# schematic.net
KiCad netlist of a schematic drawn in Altium Designer
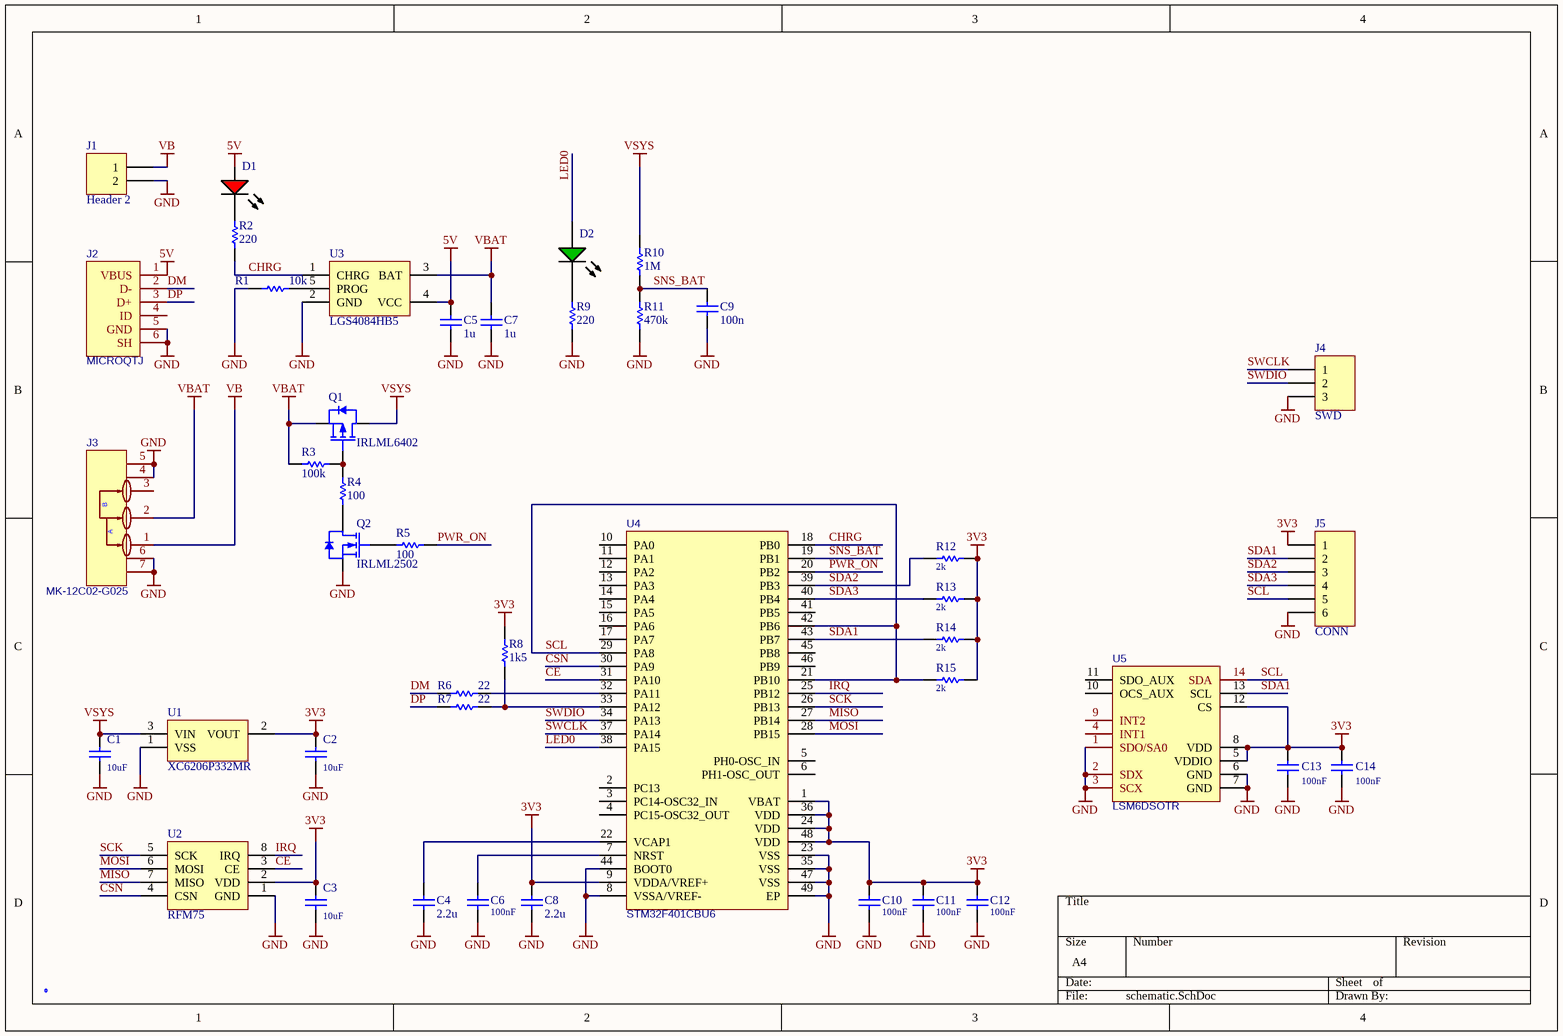
[diagram p0: schematic.SchDoc]

(export (version "E")
  (design (tool "Eeschema 10.0.6"))
  (components
    (comp (ref "C1")
      (value "10uF")
      (footprint "C0603")
      (libsource (lib "Miscellaneous Devices") (part "CAP"))
    )
    (comp (ref "C2")
      (value "10uF")
      (footprint "C0603")
      (libsource (lib "Miscellaneous Devices") (part "CAP"))
    )
    (comp (ref "C3")
      (value "10uF")
      (footprint "C0805")
      (libsource (lib "Miscellaneous Devices") (part "CAP"))
    )
    (comp (ref "C4")
      (value "2.2u")
      (footprint "C0603")
      (libsource (lib "Miscellaneous Devices") (part "Cap"))
    )
    (comp (ref "C5") (value "1u") (footprint "C0805") (libsource (lib "Miscellaneous Devices") (part "Cap")))
    (comp (ref "C6")
      (value "100nF")
      (footprint "C0402")
      (libsource (lib "Miscellaneous Devices") (part "CAP"))
    )
    (comp (ref "C7") (value "1u") (footprint "C0805") (libsource (lib "Miscellaneous Devices") (part "Cap")))
    (comp (ref "C8")
      (value "2.2u")
      (footprint "C0603")
      (libsource (lib "Miscellaneous Devices") (part "Cap"))
    )
    (comp (ref "C9")
      (value "100n")
      (footprint "C0402")
      (libsource (lib "Miscellaneous Devices") (part "Cap"))
    )
    (comp (ref "C10")
      (value "100nF")
      (footprint "C0402")
      (libsource (lib "Miscellaneous Devices") (part "CAP"))
    )
    (comp (ref "C11")
      (value "100nF")
      (footprint "C0402")
      (libsource (lib "Miscellaneous Devices") (part "CAP"))
    )
    (comp (ref "C12")
      (value "100nF")
      (footprint "C0402")
      (libsource (lib "Miscellaneous Devices") (part "CAP"))
    )
    (comp (ref "C13")
      (value "100nF")
      (footprint "C0402")
      (fields (field (name "LCSC PART NUMBER") "C131394"))
      (libsource (lib "Miscellaneous Devices") (part "CAP"))
    )
    (comp (ref "C14")
      (value "100nF")
      (footprint "C0402")
      (fields (field (name "LCSC PART NUMBER") "C131394"))
      (libsource (lib "Miscellaneous Devices") (part "CAP"))
    )
    (comp (ref "D1")
      (value "RED")
      (footprint "LED-0603-RED")
      (description "LED 0603 RED")
      (libsource (lib "Miscellaneous Devices") (part "LED-0603-RED"))
    )
    (comp (ref "D2")
      (value "GRN")
      (footprint "LED-0603-GRN")
      (description "LED 0603 GRN")
      (libsource (lib "Miscellaneous Devices") (part "LED-0603-GREEN"))
    )
    (comp (ref "J1")
      (value "Header 2")
      (footprint "HDR-1X2_2.54")
      (libsource (lib "Schlib1") (part "Header 2"))
    )
    (comp (ref "J2")
      (value "MICROQTJ")
      (footprint "CONN-USB-MICRO_#1")
      (libsource (lib "Schlib2") (part "MICROQTJ"))
    )
    (comp (ref "J3")
      (value "MK-12C02-G025")
      (footprint "SW-SMD_MK-12C02-G025")
      (fields (field (name "LCSC PART NUMBER") "C778186"))
      (libsource (lib "Schlib1") (part "MK-12C02-G025"))
    )
    (comp (ref "J4")
      (value "SWD")
      (footprint "HDR-1x3-P1.25")
      (libsource (lib "Miscellaneous Devices") (part "Header 3"))
    )
    (comp (ref "J5") (value "CONN") (footprint "HDR-1x6-P1.25") (libsource (lib "Schlib1") (part "Header 3")))
    (comp (ref "LOGO1") (value "LOGO") (footprint "LOGO") (libsource (lib "Schlib1") (part "LOGO")))
    (comp (ref "Q1") (value "IRLML6402") (footprint "SOT-23") (libsource (lib "") (part "2N7002_1")))
    (comp (ref "Q2")
      (value "IRLML2502")
      (footprint "SOT-23")
      (libsource (lib "Miscellaneous Devices") (part "2N7002"))
    )
    (comp (ref "R1")
      (value "10k")
      (footprint "R0402")
      (libsource (lib "Miscellaneous Devices") (part "Res1"))
    )
    (comp (ref "R2")
      (value "220")
      (footprint "R0402")
      (libsource (lib "Miscellaneous Devices") (part "Res1"))
    )
    (comp (ref "R3")
      (value "100k")
      (footprint "R0402")
      (libsource (lib "Miscellaneous Devices") (part "Res1"))
    )
    (comp (ref "R4")
      (value "100")
      (footprint "R0402")
      (libsource (lib "Miscellaneous Devices") (part "Res1"))
    )
    (comp (ref "R5")
      (value "100")
      (footprint "R0402")
      (libsource (lib "Miscellaneous Devices") (part "Res1"))
    )
    (comp (ref "R6") (value "22") (footprint "R0402") (libsource (lib "Miscellaneous Devices") (part "Res1")))
    (comp (ref "R7") (value "22") (footprint "R0402") (libsource (lib "Miscellaneous Devices") (part "Res1")))
    (comp (ref "R8")
      (value "1k5")
      (footprint "R0402")
      (libsource (lib "Miscellaneous Devices") (part "Res1"))
    )
    (comp (ref "R9")
      (value "220")
      (footprint "R0402")
      (libsource (lib "Miscellaneous Devices") (part "Res1"))
    )
    (comp (ref "R10")
      (value "1M")
      (footprint "R0402")
      (libsource (lib "Miscellaneous Devices") (part "Res1"))
    )
    (comp (ref "R11")
      (value "470k")
      (footprint "R0402")
      (libsource (lib "Miscellaneous Devices") (part "Res1"))
    )
    (comp (ref "R12") (value "2k") (footprint "R0402") (libsource (lib "Miscellaneous Devices") (part "RES")))
    (comp (ref "R13") (value "2k") (footprint "R0402") (libsource (lib "Miscellaneous Devices") (part "RES")))
    (comp (ref "R14") (value "2k") (footprint "R0402") (libsource (lib "Miscellaneous Devices") (part "RES")))
    (comp (ref "R15") (value "2k") (footprint "R0402") (libsource (lib "Miscellaneous Devices") (part "RES")))
    (comp (ref "U1")
      (value "XC6206P332MR")
      (footprint "SOT-23")
      (libsource (lib "Schlib1") (part "Component_4_1"))
    )
    (comp (ref "U2") (value "RFM75") (footprint "RFM75") (libsource (lib "Schlib1") (part "RFM75")))
    (comp (ref "U3")
      (value "LGS4084HB5")
      (footprint "SOT-23-5")
      (libsource (lib "Schlib1") (part "LGS4084HB5"))
    )
    (comp (ref "U4")
      (value "STM32F401CBU6")
      (footprint "UFQFPN-48_L7.0-W7.0")
      (fields (field (name "LCSC PART NUMBER") "C118825"))
      (libsource (lib "Schlib1") (part "STM32F401CBU6"))
    )
    (comp (ref "U5")
      (value "LSM6DSOTR")
      (footprint "LGA-14_L3.0-W2.5-P0.50-TL")
      (fields (field (name "LCSC PART NUMBER") "C2655100"))
      (libsource (lib "Schlib1") (part "LSM6DSOTR"))
    )
  )
  (nets
    (net (code "1") (name "/CE") (class "Default")
      (node (ref "U2") (pin "3") (pinfunction "CE_3") (pintype "passive"))
      (node (ref "U4") (pin "31") (pinfunction "PA10_31") (pintype "passive"))
    )
    (net (code "2") (name "/CHRG") (class "Default")
      (node (ref "R2") (pin "1") (pinfunction "1_1") (pintype "passive"))
      (node (ref "U3") (pin "1") (pinfunction "CHRG_1") (pintype "passive"))
      (node (ref "U4") (pin "18") (pinfunction "PB0_18") (pintype "passive"))
    )
    (net (code "3") (name "/CSN") (class "Default")
      (node (ref "U2") (pin "4") (pinfunction "CSN_4") (pintype "passive"))
      (node (ref "U4") (pin "30") (pinfunction "PA9_30") (pintype "passive"))
    )
    (net (code "4") (name "/DM") (class "Default")
      (node (ref "J2") (pin "2") (pinfunction "D-_2") (pintype "passive"))
      (node (ref "R6") (pin "2") (pinfunction "2_2") (pintype "passive"))
    )
    (net (code "5") (name "/DP") (class "Default")
      (node (ref "J2") (pin "3") (pinfunction "D+_3") (pintype "passive"))
      (node (ref "R7") (pin "2") (pinfunction "2_2") (pintype "passive"))
    )
    (net (code "6") (name "/IRQ") (class "Default")
      (node (ref "U2") (pin "8") (pinfunction "IRQ_8") (pintype "passive"))
      (node (ref "U4") (pin "25") (pinfunction "PB12_25") (pintype "passive"))
    )
    (net (code "7") (name "/LED0") (class "Default")
      (node (ref "D2") (pin "1") (pinfunction "A_1") (pintype "passive"))
      (node (ref "U4") (pin "38") (pinfunction "PA15_38") (pintype "passive"))
    )
    (net (code "8") (name "/MISO") (class "Default")
      (node (ref "U2") (pin "7") (pinfunction "MISO_7") (pintype "passive"))
      (node (ref "U4") (pin "27") (pinfunction "PB14_27") (pintype "passive"))
    )
    (net (code "9") (name "/MOSI") (class "Default")
      (node (ref "U2") (pin "6") (pinfunction "MOSI_6") (pintype "passive"))
      (node (ref "U4") (pin "28") (pinfunction "PB15_28") (pintype "passive"))
    )
    (net (code "10") (name "/PWR_ON") (class "Default")
      (node (ref "R5") (pin "1") (pinfunction "1_1") (pintype "passive"))
      (node (ref "U4") (pin "20") (pinfunction "PB2_20") (pintype "passive"))
    )
    (net (code "11") (name "/SCK") (class "Default")
      (node (ref "U2") (pin "5") (pinfunction "SCK_5") (pintype "passive"))
      (node (ref "U4") (pin "26") (pinfunction "PB13_26") (pintype "passive"))
    )
    (net (code "12") (name "/SCL") (class "Default")
      (node (ref "J5") (pin "5") (pinfunction "5_5") (pintype "passive"))
      (node (ref "R15") (pin "2") (pinfunction "2_2") (pintype "passive"))
      (node (ref "U4") (pin "21") (pinfunction "PB10_21") (pintype "passive"))
      (node (ref "U4") (pin "29") (pinfunction "PA8_29") (pintype "passive"))
      (node (ref "U4") (pin "42") (pinfunction "PB6_42") (pintype "passive"))
      (node (ref "U5") (pin "14") (pinfunction "SDA_14") (pintype "passive"))
    )
    (net (code "13") (name "/SDA1") (class "Default")
      (node (ref "J5") (pin "2") (pinfunction "2_2") (pintype "passive"))
      (node (ref "R14") (pin "2") (pinfunction "2_2") (pintype "passive"))
      (node (ref "U4") (pin "43") (pinfunction "PB7_43") (pintype "passive"))
      (node (ref "U5") (pin "13") (pinfunction "SCL_13") (pintype "passive"))
    )
    (net (code "14") (name "/SDA2") (class "Default")
      (node (ref "J5") (pin "3") (pinfunction "3_3") (pintype "passive"))
      (node (ref "R12") (pin "2") (pinfunction "2_2") (pintype "passive"))
      (node (ref "U4") (pin "39") (pinfunction "PB3_39") (pintype "passive"))
    )
    (net (code "15") (name "/SDA3") (class "Default")
      (node (ref "J5") (pin "4") (pinfunction "4_4") (pintype "passive"))
      (node (ref "R13") (pin "2") (pinfunction "2_2") (pintype "passive"))
      (node (ref "U4") (pin "40") (pinfunction "PB4_40") (pintype "passive"))
    )
    (net (code "16") (name "/SNS_BAT") (class "Default")
      (node (ref "C9") (pin "2") (pinfunction "2_2") (pintype "passive"))
      (node (ref "R10") (pin "1") (pinfunction "1_1") (pintype "passive"))
      (node (ref "R11") (pin "2") (pinfunction "2_2") (pintype "passive"))
      (node (ref "U4") (pin "19") (pinfunction "PB1_19") (pintype "passive"))
    )
    (net (code "17") (name "/SWCLK") (class "Default")
      (node (ref "J4") (pin "1") (pinfunction "1_1") (pintype "passive"))
      (node (ref "U4") (pin "37") (pinfunction "PA14_37") (pintype "passive"))
    )
    (net (code "18") (name "/SWDIO") (class "Default")
      (node (ref "J4") (pin "2") (pinfunction "2_2") (pintype "passive"))
      (node (ref "U4") (pin "34") (pinfunction "PA13_34") (pintype "passive"))
    )
    (net (code "19") (name "3V3") (class "Default")
      (node (ref "C10") (pin "2") (pinfunction "2_2") (pintype "passive"))
      (node (ref "C11") (pin "2") (pinfunction "2_2") (pintype "passive"))
      (node (ref "C12") (pin "2") (pinfunction "2_2") (pintype "passive"))
      (node (ref "C13") (pin "2") (pinfunction "2_2") (pintype "passive"))
      (node (ref "C14") (pin "2") (pinfunction "2_2") (pintype "passive"))
      (node (ref "C2") (pin "2") (pinfunction "2_2") (pintype "passive"))
      (node (ref "C3") (pin "2") (pinfunction "2_2") (pintype "passive"))
      (node (ref "C8") (pin "2") (pinfunction "2_2") (pintype "passive"))
      (node (ref "J5") (pin "1") (pinfunction "1_1") (pintype "passive"))
      (node (ref "R12") (pin "1") (pinfunction "1_1") (pintype "passive"))
      (node (ref "R13") (pin "1") (pinfunction "1_1") (pintype "passive"))
      (node (ref "R14") (pin "1") (pinfunction "1_1") (pintype "passive"))
      (node (ref "R15") (pin "1") (pinfunction "1_1") (pintype "passive"))
      (node (ref "R8") (pin "1") (pinfunction "1_1") (pintype "passive"))
      (node (ref "U1") (pin "2") (pinfunction "VOUT_2") (pintype "passive"))
      (node (ref "U2") (pin "2") (pinfunction "VDD_2") (pintype "passive"))
      (node (ref "U4") (pin "1") (pinfunction "VBAT_1") (pintype "passive"))
      (node (ref "U4") (pin "24") (pinfunction "VDD_24") (pintype "passive"))
      (node (ref "U4") (pin "36") (pinfunction "VDD_36") (pintype "passive"))
      (node (ref "U4") (pin "48") (pinfunction "VDD_48") (pintype "passive"))
      (node (ref "U4") (pin "9") (pinfunction "VDDA/VREF+_9") (pintype "passive"))
      (node (ref "U5") (pin "12") (pinfunction "CS_12") (pintype "passive"))
      (node (ref "U5") (pin "5") (pinfunction "VDDIO_5") (pintype "passive"))
      (node (ref "U5") (pin "8") (pinfunction "VDD_8") (pintype "passive"))
    )
    (net (code "20") (name "5V") (class "Default")
      (node (ref "C5") (pin "2") (pinfunction "2_2") (pintype "passive"))
      (node (ref "D1") (pin "1") (pinfunction "A_1") (pintype "passive"))
      (node (ref "J2") (pin "1") (pinfunction "VBUS_1") (pintype "passive"))
      (node (ref "U3") (pin "4") (pinfunction "VCC_4") (pintype "passive"))
    )
    (net (code "21") (name "GND") (class "Default")
      (node (ref "C1") (pin "1") (pinfunction "1_1") (pintype "passive"))
      (node (ref "C10") (pin "1") (pinfunction "1_1") (pintype "passive"))
      (node (ref "C11") (pin "1") (pinfunction "1_1") (pintype "passive"))
      (node (ref "C12") (pin "1") (pinfunction "1_1") (pintype "passive"))
      (node (ref "C13") (pin "1") (pinfunction "1_1") (pintype "passive"))
      (node (ref "C14") (pin "1") (pinfunction "1_1") (pintype "passive"))
      (node (ref "C2") (pin "1") (pinfunction "1_1") (pintype "passive"))
      (node (ref "C3") (pin "1") (pinfunction "1_1") (pintype "passive"))
      (node (ref "C4") (pin "1") (pinfunction "1_1") (pintype "passive"))
      (node (ref "C5") (pin "1") (pinfunction "1_1") (pintype "passive"))
      (node (ref "C6") (pin "1") (pinfunction "1_1") (pintype "passive"))
      (node (ref "C7") (pin "1") (pinfunction "1_1") (pintype "passive"))
      (node (ref "C8") (pin "1") (pinfunction "1_1") (pintype "passive"))
      (node (ref "C9") (pin "1") (pinfunction "1_1") (pintype "passive"))
      (node (ref "J1") (pin "2") (pinfunction "2_2") (pintype "passive"))
      (node (ref "J2") (pin "5") (pinfunction "GND_5") (pintype "passive"))
      (node (ref "J2") (pin "6") (pinfunction "SH_6") (pintype "passive"))
      (node (ref "J3") (pin "4") (pinfunction "4_4") (pintype "passive"))
      (node (ref "J3") (pin "5") (pinfunction "5_5") (pintype "passive"))
      (node (ref "J3") (pin "6") (pinfunction "6_6") (pintype "passive"))
      (node (ref "J3") (pin "7") (pinfunction "7_7") (pintype "passive"))
      (node (ref "J4") (pin "3") (pinfunction "3_3") (pintype "passive"))
      (node (ref "J5") (pin "6") (pinfunction "6_6") (pintype "passive"))
      (node (ref "Q2") (pin "2") (pinfunction "SOURCE_2") (pintype "passive"))
      (node (ref "R1") (pin "2") (pinfunction "2_2") (pintype "passive"))
      (node (ref "R11") (pin "1") (pinfunction "1_1") (pintype "passive"))
      (node (ref "R9") (pin "1") (pinfunction "1_1") (pintype "passive"))
      (node (ref "U1") (pin "1") (pinfunction "VSS_1") (pintype "passive"))
      (node (ref "U2") (pin "1") (pinfunction "GND_1") (pintype "passive"))
      (node (ref "U3") (pin "2") (pinfunction "GND_2") (pintype "passive"))
      (node (ref "U4") (pin "23") (pinfunction "VSS_23") (pintype "passive"))
      (node (ref "U4") (pin "35") (pinfunction "VSS_35") (pintype "passive"))
      (node (ref "U4") (pin "44") (pinfunction "BOOT0_44") (pintype "passive"))
      (node (ref "U4") (pin "47") (pinfunction "VSS_47") (pintype "passive"))
      (node (ref "U4") (pin "49") (pinfunction "EP_49") (pintype "passive"))
      (node (ref "U4") (pin "8") (pinfunction "VSSA/VREF-_8") (pintype "passive"))
      (node (ref "U5") (pin "1") (pinfunction "SDO/SA0_1") (pintype "passive"))
      (node (ref "U5") (pin "2") (pinfunction "SDX_2") (pintype "passive"))
      (node (ref "U5") (pin "3") (pinfunction "SCX_3") (pintype "passive"))
      (node (ref "U5") (pin "6") (pinfunction "GND_6") (pintype "passive"))
      (node (ref "U5") (pin "7") (pinfunction "GND_7") (pintype "passive"))
    )
    (net (code "22") (name "Net-(D1-K)") (class "Default")
      (node (ref "D1") (pin "2") (pinfunction "K_2") (pintype "passive"))
      (node (ref "R2") (pin "2") (pinfunction "2_2") (pintype "passive"))
    )
    (net (code "23") (name "Net-(D2-K)") (class "Default")
      (node (ref "D2") (pin "2") (pinfunction "K_2") (pintype "passive"))
      (node (ref "R9") (pin "2") (pinfunction "2_2") (pintype "passive"))
    )
    (net (code "24") (name "Net-(Q1-GATE)") (class "Default")
      (node (ref "Q1") (pin "1") (pinfunction "GATE_1") (pintype "passive"))
      (node (ref "R3") (pin "1") (pinfunction "1_1") (pintype "passive"))
      (node (ref "R4") (pin "2") (pinfunction "2_2") (pintype "passive"))
    )
    (net (code "25") (name "Net-(Q2-DRAIN)") (class "Default")
      (node (ref "Q2") (pin "3") (pinfunction "DRAIN_3") (pintype "passive"))
      (node (ref "R4") (pin "1") (pinfunction "1_1") (pintype "passive"))
    )
    (net (code "26") (name "Net-(Q2-GATE)") (class "Default")
      (node (ref "Q2") (pin "1") (pinfunction "GATE_1") (pintype "passive"))
      (node (ref "R5") (pin "2") (pinfunction "2_2") (pintype "passive"))
    )
    (net (code "27") (name "Net-(U3-PROG)") (class "Default")
      (node (ref "R1") (pin "1") (pinfunction "1_1") (pintype "passive"))
      (node (ref "U3") (pin "5") (pinfunction "PROG_5") (pintype "passive"))
    )
    (net (code "28") (name "Net-(U4-NRST)") (class "Default")
      (node (ref "C6") (pin "2") (pinfunction "2_2") (pintype "passive"))
      (node (ref "U4") (pin "7") (pinfunction "NRST_7") (pintype "passive"))
    )
    (net (code "29") (name "Net-(U4-PA11)") (class "Default")
      (node (ref "R6") (pin "1") (pinfunction "1_1") (pintype "passive"))
      (node (ref "U4") (pin "32") (pinfunction "PA11_32") (pintype "passive"))
    )
    (net (code "30") (name "Net-(U4-PA12)") (class "Default")
      (node (ref "R7") (pin "1") (pinfunction "1_1") (pintype "passive"))
      (node (ref "R8") (pin "2") (pinfunction "2_2") (pintype "passive"))
      (node (ref "U4") (pin "33") (pinfunction "PA12_33") (pintype "passive"))
    )
    (net (code "31") (name "Net-(U4-VCAP1)") (class "Default")
      (node (ref "C4") (pin "2") (pinfunction "2_2") (pintype "passive"))
      (node (ref "U4") (pin "22") (pinfunction "VCAP1_22") (pintype "passive"))
    )
    (net (code "32") (name "VB") (class "Default")
      (node (ref "J1") (pin "1") (pinfunction "1_1") (pintype "passive"))
      (node (ref "J3") (pin "1") (pinfunction "1_1") (pintype "passive"))
    )
    (net (code "33") (name "VBAT") (class "Default")
      (node (ref "C7") (pin "2") (pinfunction "2_2") (pintype "passive"))
      (node (ref "J3") (pin "2") (pinfunction "2_2") (pintype "passive"))
      (node (ref "Q1") (pin "2") (pinfunction "SOURCE_2") (pintype "passive"))
      (node (ref "R3") (pin "2") (pinfunction "2_2") (pintype "passive"))
      (node (ref "U3") (pin "3") (pinfunction "BAT_3") (pintype "passive"))
    )
    (net (code "34") (name "VSYS") (class "Default")
      (node (ref "C1") (pin "2") (pinfunction "2_2") (pintype "passive"))
      (node (ref "Q1") (pin "3") (pinfunction "DRAIN_3") (pintype "passive"))
      (node (ref "R10") (pin "2") (pinfunction "2_2") (pintype "passive"))
      (node (ref "U1") (pin "3") (pinfunction "VIN_3") (pintype "passive"))
    )
    (net (code "35") (name "unconnected-(J2-ID-Pad4)") (class "Default")
      (node (ref "J2") (pin "4") (pinfunction "ID_4") (pintype "passive"))
    )
    (net (code "36") (name "unconnected-(J3-Pad3)") (class "Default")
      (node (ref "J3") (pin "3") (pinfunction "3_3") (pintype "passive"))
    )
    (net (code "37") (name "unconnected-(U4-PA0-Pad10)") (class "Default")
      (node (ref "U4") (pin "10") (pinfunction "PA0_10") (pintype "passive"))
    )
    (net (code "38") (name "unconnected-(U4-PA1-Pad11)") (class "Default")
      (node (ref "U4") (pin "11") (pinfunction "PA1_11") (pintype "passive"))
    )
    (net (code "39") (name "unconnected-(U4-PA2-Pad12)") (class "Default")
      (node (ref "U4") (pin "12") (pinfunction "PA2_12") (pintype "passive"))
    )
    (net (code "40") (name "unconnected-(U4-PA3-Pad13)") (class "Default")
      (node (ref "U4") (pin "13") (pinfunction "PA3_13") (pintype "passive"))
    )
    (net (code "41") (name "unconnected-(U4-PA4-Pad14)") (class "Default")
      (node (ref "U4") (pin "14") (pinfunction "PA4_14") (pintype "passive"))
    )
    (net (code "42") (name "unconnected-(U4-PA5-Pad15)") (class "Default")
      (node (ref "U4") (pin "15") (pinfunction "PA5_15") (pintype "passive"))
    )
    (net (code "43") (name "unconnected-(U4-PA6-Pad16)") (class "Default")
      (node (ref "U4") (pin "16") (pinfunction "PA6_16") (pintype "passive"))
    )
    (net (code "44") (name "unconnected-(U4-PA7-Pad17)") (class "Default")
      (node (ref "U4") (pin "17") (pinfunction "PA7_17") (pintype "passive"))
    )
    (net (code "45") (name "unconnected-(U4-PB5-Pad41)") (class "Default")
      (node (ref "U4") (pin "41") (pinfunction "PB5_41") (pintype "passive"))
    )
    (net (code "46") (name "unconnected-(U4-PB8-Pad45)") (class "Default")
      (node (ref "U4") (pin "45") (pinfunction "PB8_45") (pintype "passive"))
    )
    (net (code "47") (name "unconnected-(U4-PB9-Pad46)") (class "Default")
      (node (ref "U4") (pin "46") (pinfunction "PB9_46") (pintype "passive"))
    )
    (net (code "48") (name "unconnected-(U4-PC13-Pad2)") (class "Default")
      (node (ref "U4") (pin "2") (pinfunction "PC13_2") (pintype "passive"))
    )
    (net (code "49") (name "unconnected-(U4-PC14-OSC32_IN-Pad3)") (class "Default")
      (node (ref "U4") (pin "3") (pinfunction "PC14-OSC32_IN_3") (pintype "passive"))
    )
    (net (code "50") (name "unconnected-(U4-PC15-OSC32_OUT-Pad4)") (class "Default")
      (node (ref "U4") (pin "4") (pinfunction "PC15-OSC32_OUT_4") (pintype "passive"))
    )
    (net (code "51") (name "unconnected-(U4-PH0-OSC_IN-Pad5)") (class "Default")
      (node (ref "U4") (pin "5") (pinfunction "PH0-OSC_IN_5") (pintype "passive"))
    )
    (net (code "52") (name "unconnected-(U4-PH1-OSC_OUT-Pad6)") (class "Default")
      (node (ref "U4") (pin "6") (pinfunction "PH1-OSC_OUT_6") (pintype "passive"))
    )
    (net (code "53") (name "unconnected-(U5-INT1-Pad4)") (class "Default")
      (node (ref "U5") (pin "4") (pinfunction "INT1_4") (pintype "passive"))
    )
    (net (code "54") (name "unconnected-(U5-INT2-Pad9)") (class "Default")
      (node (ref "U5") (pin "9") (pinfunction "INT2_9") (pintype "passive"))
    )
    (net (code "55") (name "unconnected-(U5-OCS_AUX-Pad10)") (class "Default")
      (node (ref "U5") (pin "10") (pinfunction "OCS_AUX_10") (pintype "passive"))
    )
    (net (code "56") (name "unconnected-(U5-SDO_AUX-Pad11)") (class "Default")
      (node (ref "U5") (pin "11") (pinfunction "SDO_AUX_11") (pintype "passive"))
    )
  )
)
